# Driver3.net
KiCad netlist of a schematic drawn in Altium Designer
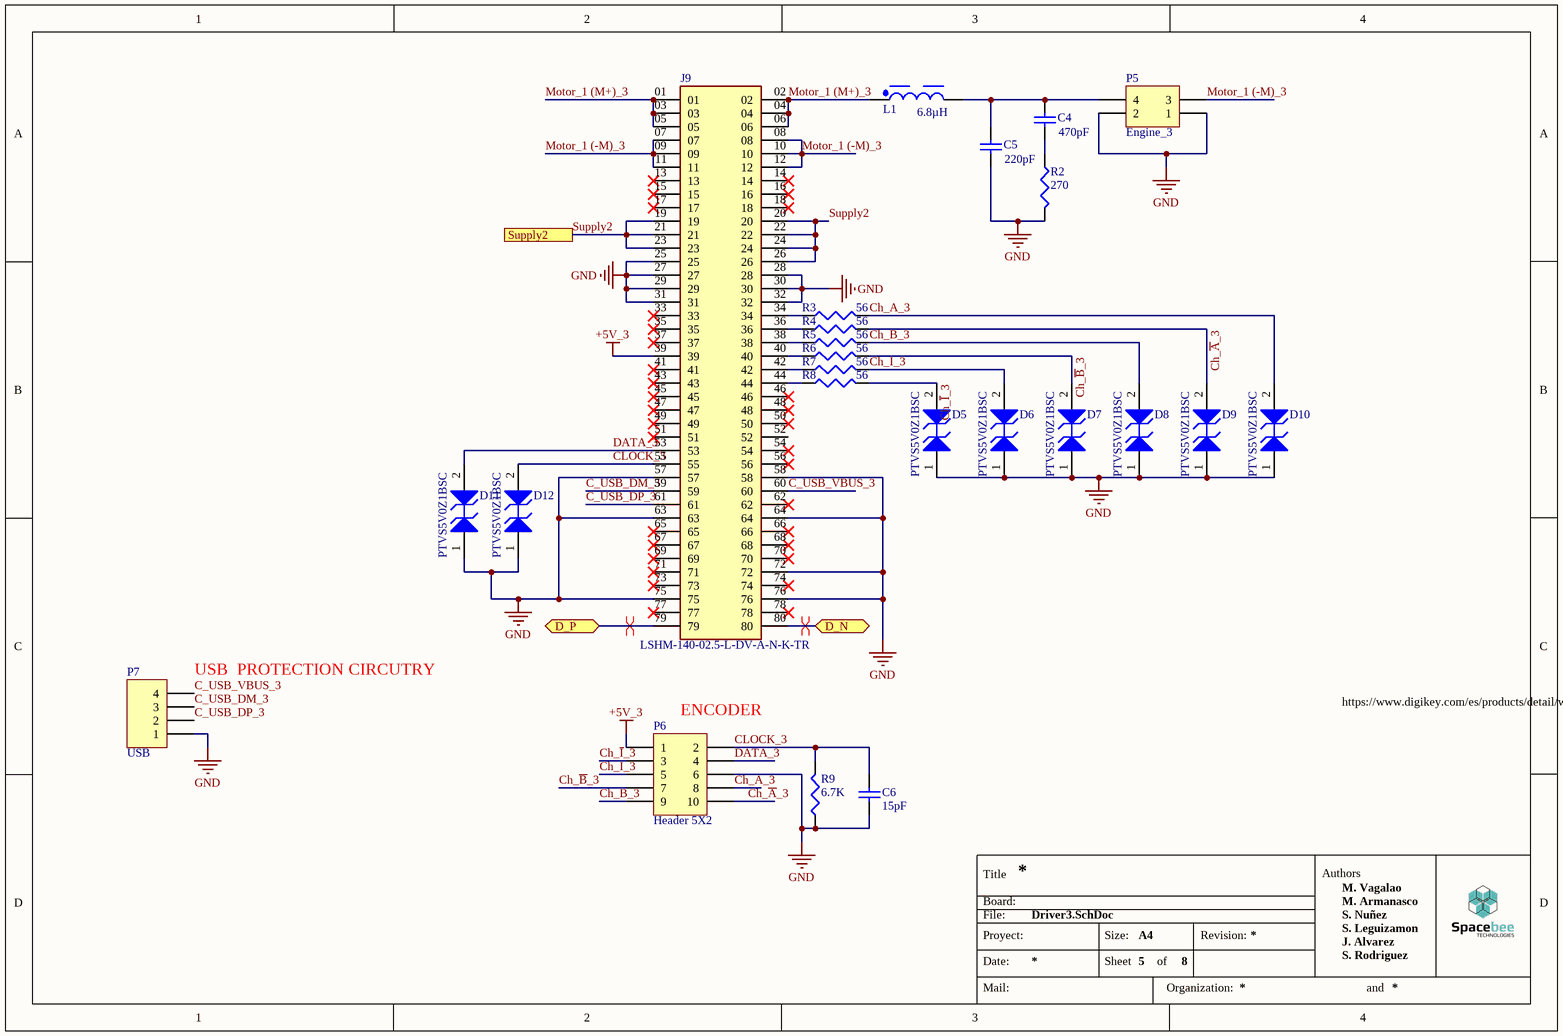
[diagram p0: Driver3.SchDoc]

(export (version "E")
  (design (tool "Eeschema 10.0.6"))
  (components
    (comp (ref "C4")
      (value "470pF")
      (footprint "1608[0603]")
      (description "Capacitor (Semiconductor SIM Model)")
      (fields (field (name "Comment") "Cap Semi") (field (name "PUBLISHER") "Altium Limited"))
      (libsource (lib "Miscellaneous Devices") (part "Cap Semi"))
    )
    (comp (ref "C5")
      (value "220pF")
      (footprint "1608[0603]")
      (description "Capacitor (Semiconductor SIM Model)")
      (fields (field (name "Comment") "Cap Semi") (field (name "PUBLISHER") "Altium Limited"))
      (libsource (lib "Miscellaneous Devices") (part "Cap Semi"))
    )
    (comp (ref "C6")
      (value "15pF")
      (footprint "6-0805_L")
      (description "Capacitor (Semiconductor SIM Model)")
      (fields (field (name "Comment") "Cap Semi") (field (name "PUBLISHER") "Altium Limited"))
      (libsource (lib "SpaceBee") (part "Cap 0805"))
    )
    (comp (ref "D5")
      (value "PTVS5V0Z1BSC")
      (footprint "SOD993B")
      (fields (field (name "MANUFACTURER") "On Semiconductor") (field (name "PARTNUMBER") "1SMB16CAT3"))
      (libsource (lib "DriverLib") (part "PTVS5V0Z1BSC"))
    )
    (comp (ref "D6")
      (value "PTVS5V0Z1BSC")
      (footprint "SOD993B")
      (fields (field (name "MANUFACTURER") "On Semiconductor") (field (name "PARTNUMBER") "1SMB16CAT3"))
      (libsource (lib "DriverLib") (part "PTVS5V0Z1BSC"))
    )
    (comp (ref "D7")
      (value "PTVS5V0Z1BSC")
      (footprint "SOD993B")
      (fields (field (name "MANUFACTURER") "On Semiconductor") (field (name "PARTNUMBER") "1SMB16CAT3"))
      (libsource (lib "DriverLib") (part "PTVS5V0Z1BSC"))
    )
    (comp (ref "D8")
      (value "PTVS5V0Z1BSC")
      (footprint "SOD993B")
      (fields (field (name "MANUFACTURER") "On Semiconductor") (field (name "PARTNUMBER") "1SMB16CAT3"))
      (libsource (lib "DriverLib") (part "PTVS5V0Z1BSC"))
    )
    (comp (ref "D9")
      (value "PTVS5V0Z1BSC")
      (footprint "SOD993B")
      (fields (field (name "MANUFACTURER") "On Semiconductor") (field (name "PARTNUMBER") "1SMB16CAT3"))
      (libsource (lib "DriverLib") (part "PTVS5V0Z1BSC"))
    )
    (comp (ref "D10")
      (value "PTVS5V0Z1BSC")
      (footprint "SOD993B")
      (fields (field (name "MANUFACTURER") "On Semiconductor") (field (name "PARTNUMBER") "1SMB16CAT3"))
      (libsource (lib "DriverLib") (part "PTVS5V0Z1BSC"))
    )
    (comp (ref "D11")
      (value "PTVS5V0Z1BSC")
      (footprint "SOD993B")
      (fields (field (name "MANUFACTURER") "On Semiconductor") (field (name "PARTNUMBER") "1SMB16CAT3"))
      (libsource (lib "DriverLib") (part "PTVS5V0Z1BSC"))
    )
    (comp (ref "D12")
      (value "PTVS5V0Z1BSC")
      (footprint "SOD993B")
      (fields (field (name "MANUFACTURER") "On Semiconductor") (field (name "PARTNUMBER") "1SMB16CAT3"))
      (libsource (lib "DriverLib") (part "PTVS5V0Z1BSC"))
    )
    (comp (ref "J9")
      (value "LSHM-140-02.5-L-DV-A-N-K-TR")
      (footprint "SAMTEC_LSHM-140-02.5-L-DV-A-N-K-TR")
      (description "LSHM - Samtec 0.50mm Razor Beam High-Speed Hermaphroditic Terminal / Socket Strip.")
      (libsource (lib "DriverLib") (part "LSHM-140-02.5-L-DV-A-N-K-TR"))
    )
    (comp (ref "L1")
      (value "6.8µH")
      (footprint "WE-XHMA_6060")
      (description "WE-XHMA SMD Power Inductor, size 1090, 6.8µH, 10.5A, 7.16mΩ")
      (fields
        (field (name "MANUFACTURER PART NUMBER") "78439369068")
        (field (name "MANUFACTURER") "Wurth Elektronik")
      )
      (libsource (lib "DriverLib") (part "78439369068"))
    )
    (comp (ref "P5")
      (value "Engine_3")
      (footprint "MOLEX_1724480004")
      (description "Header, 2-Pin, Dual row")
      (fields (field (name "PUBLISHER") "Altium Limited"))
      (libsource (lib "SpaceBee") (part "Header 2X2"))
    )
    (comp (ref "P6")
      (value "Header 5X2")
      (footprint "CONN_HIF3FC-14PA-2.54DS(71)_HIR")
      (description "Header, 5-Pin, Dual row")
      (fields (field (name "PUBLISHER") "Altium Limited"))
      (libsource (lib "DriverLib") (part "Header 5X2"))
    )
    (comp (ref "P7")
      (value "USB")
      (footprint "Header 4 SMD")
      (description "Header, 4-Pin")
      (fields (field (name "PUBLISHER") "Altium Limited"))
      (libsource (lib "SpaceBee") (part "Header 4 SMD"))
    )
    (comp (ref "R2")
      (value "270")
      (footprint "J1-0603")
      (description "Resistor")
      (fields (field (name "Comment") "Res3") (field (name "PUBLISHER") "Altium Limited"))
      (libsource (lib "Miscellaneous Devices") (part "Res3"))
    )
    (comp (ref "R3")
      (value "56")
      (footprint "J1-0603")
      (description "Resistor")
      (fields (field (name "Comment") "Res3") (field (name "PUBLISHER") "Altium Limited"))
      (libsource (lib "Miscellaneous Devices") (part "Res3"))
    )
    (comp (ref "R4")
      (value "56")
      (footprint "J1-0603")
      (description "Resistor")
      (fields (field (name "Comment") "Res3") (field (name "PUBLISHER") "Altium Limited"))
      (libsource (lib "Miscellaneous Devices") (part "Res3"))
    )
    (comp (ref "R5")
      (value "56")
      (footprint "J1-0603")
      (description "Resistor")
      (fields (field (name "Comment") "Res3") (field (name "PUBLISHER") "Altium Limited"))
      (libsource (lib "Miscellaneous Devices") (part "Res3"))
    )
    (comp (ref "R6")
      (value "56")
      (footprint "J1-0603")
      (description "Resistor")
      (fields (field (name "Comment") "Res3") (field (name "PUBLISHER") "Altium Limited"))
      (libsource (lib "Miscellaneous Devices") (part "Res3"))
    )
    (comp (ref "R7")
      (value "56")
      (footprint "J1-0603")
      (description "Resistor")
      (fields (field (name "Comment") "Res3") (field (name "PUBLISHER") "Altium Limited"))
      (libsource (lib "Miscellaneous Devices") (part "Res3"))
    )
    (comp (ref "R8")
      (value "56")
      (footprint "J1-0603")
      (description "Resistor")
      (fields (field (name "Comment") "Res3") (field (name "PUBLISHER") "Altium Limited"))
      (libsource (lib "Miscellaneous Devices") (part "Res3"))
    )
    (comp (ref "R9")
      (value "6.7K")
      (footprint "J1-0603")
      (description "Resistor")
      (fields (field (name "Comment") "Res3") (field (name "PUBLISHER") "Altium Limited"))
      (libsource (lib "Miscellaneous Devices") (part "Res3"))
    )
  )
  (nets
    (net (code "1") (name "+5V_3") (class "Default")
      (node (ref "J9") (pin "39") (pinfunction "39_39") (pintype "passive"))
      (node (ref "P6") (pin "1") (pinfunction "1_1") (pintype "passive"))
    )
    (net (code "2") (name "/CLOCK_3") (class "Default")
      (node (ref "C6") (pin "2") (pinfunction "2_2") (pintype "passive"))
      (node (ref "D12") (pin "2") (pinfunction "A2_2") (pintype "passive"))
      (node (ref "J9") (pin "55") (pinfunction "55_55") (pintype "passive"))
      (node (ref "P6") (pin "2") (pinfunction "2_2") (pintype "passive"))
      (node (ref "R9") (pin "2") (pinfunction "2_2") (pintype "passive"))
    )
    (net (code "3") (name "/C_USB_DM_3") (class "Default")
      (node (ref "J9") (pin "59") (pinfunction "59_59") (pintype "passive"))
      (node (ref "P7") (pin "3") (pinfunction "3_3") (pintype "passive"))
    )
    (net (code "4") (name "/C_USB_DP_3") (class "Default")
      (node (ref "J9") (pin "61") (pinfunction "61_61") (pintype "passive"))
      (node (ref "P7") (pin "2") (pinfunction "2_2") (pintype "passive"))
    )
    (net (code "5") (name "/C_USB_VBUS_3") (class "Default")
      (node (ref "J9") (pin "60") (pinfunction "60_60") (pintype "passive"))
      (node (ref "P7") (pin "4") (pinfunction "4_4") (pintype "passive"))
    )
    (net (code "6") (name "/Ch_A_3") (class "Default")
      (node (ref "D10") (pin "2") (pinfunction "A2_2") (pintype "passive"))
      (node (ref "P6") (pin "8") (pinfunction "8_8") (pintype "passive"))
      (node (ref "R3") (pin "2") (pinfunction "2_2") (pintype "passive"))
    )
    (net (code "7") (name "/Ch_B_3") (class "Default")
      (node (ref "D8") (pin "2") (pinfunction "A2_2") (pintype "passive"))
      (node (ref "P6") (pin "9") (pinfunction "9_9") (pintype "passive"))
      (node (ref "R5") (pin "2") (pinfunction "2_2") (pintype "passive"))
    )
    (net (code "8") (name "/Ch_I_3") (class "Default")
      (node (ref "D6") (pin "2") (pinfunction "A2_2") (pintype "passive"))
      (node (ref "P6") (pin "5") (pinfunction "5_5") (pintype "passive"))
      (node (ref "R7") (pin "2") (pinfunction "2_2") (pintype "passive"))
    )
    (net (code "9") (name "/Ch_~{A}_3") (class "Default")
      (node (ref "D9") (pin "2") (pinfunction "A2_2") (pintype "passive"))
      (node (ref "P6") (pin "10") (pinfunction "10_10") (pintype "passive"))
      (node (ref "R4") (pin "2") (pinfunction "2_2") (pintype "passive"))
    )
    (net (code "10") (name "/Ch_~{B}_3") (class "Default")
      (node (ref "D7") (pin "2") (pinfunction "A2_2") (pintype "passive"))
      (node (ref "P6") (pin "7") (pinfunction "7_7") (pintype "passive"))
      (node (ref "R6") (pin "2") (pinfunction "2_2") (pintype "passive"))
    )
    (net (code "11") (name "/Ch_~{I}_3") (class "Default")
      (node (ref "D5") (pin "2") (pinfunction "A2_2") (pintype "passive"))
      (node (ref "P6") (pin "3") (pinfunction "3_3") (pintype "passive"))
      (node (ref "R8") (pin "2") (pinfunction "2_2") (pintype "passive"))
    )
    (net (code "12") (name "/DATA_3") (class "Default")
      (node (ref "D11") (pin "2") (pinfunction "A2_2") (pintype "passive"))
      (node (ref "J9") (pin "53") (pinfunction "53_53") (pintype "passive"))
      (node (ref "P6") (pin "4") (pinfunction "4_4") (pintype "passive"))
    )
    (net (code "13") (name "/D_N") (class "Default")
      (node (ref "J9") (pin "80") (pinfunction "80_80") (pintype "passive"))
    )
    (net (code "14") (name "/D_P") (class "Default")
      (node (ref "J9") (pin "79") (pinfunction "79_79") (pintype "passive"))
    )
    (net (code "15") (name "/Motor_1 (-M)_3") (class "Default")
      (node (ref "J9") (pin "07") (pinfunction "07_07") (pintype "passive"))
      (node (ref "J9") (pin "08") (pinfunction "08_08") (pintype "passive"))
      (node (ref "J9") (pin "09") (pinfunction "09_09") (pintype "passive"))
      (node (ref "J9") (pin "10") (pinfunction "10_10") (pintype "passive"))
      (node (ref "J9") (pin "11") (pinfunction "11_11") (pintype "passive"))
      (node (ref "J9") (pin "12") (pinfunction "12_12") (pintype "passive"))
      (node (ref "P5") (pin "3") (pinfunction "3_3") (pintype "passive"))
    )
    (net (code "16") (name "/Motor_1 (M+)_3") (class "Default")
      (node (ref "J9") (pin "01") (pinfunction "01_01") (pintype "passive"))
      (node (ref "J9") (pin "02") (pinfunction "02_02") (pintype "passive"))
      (node (ref "J9") (pin "03") (pinfunction "03_03") (pintype "passive"))
      (node (ref "J9") (pin "04") (pinfunction "04_04") (pintype "passive"))
      (node (ref "J9") (pin "05") (pinfunction "05_05") (pintype "passive"))
      (node (ref "J9") (pin "06") (pinfunction "06_06") (pintype "passive"))
      (node (ref "L1") (pin "1") (pinfunction "1_1") (pintype "passive"))
    )
    (net (code "17") (name "/Supply2") (class "Default")
      (node (ref "J9") (pin "19") (pinfunction "19_19") (pintype "passive"))
      (node (ref "J9") (pin "20") (pinfunction "20_20") (pintype "passive"))
      (node (ref "J9") (pin "21") (pinfunction "21_21") (pintype "passive"))
      (node (ref "J9") (pin "22") (pinfunction "22_22") (pintype "passive"))
      (node (ref "J9") (pin "23") (pinfunction "23_23") (pintype "passive"))
      (node (ref "J9") (pin "24") (pinfunction "24_24") (pintype "passive"))
      (node (ref "J9") (pin "26") (pinfunction "26_26") (pintype "passive"))
    )
    (net (code "18") (name "GND") (class "Default")
      (node (ref "C5") (pin "2") (pinfunction "2_2") (pintype "passive"))
      (node (ref "C6") (pin "1") (pinfunction "1_1") (pintype "passive"))
      (node (ref "D10") (pin "1") (pinfunction "A1_1") (pintype "passive"))
      (node (ref "D11") (pin "1") (pinfunction "A1_1") (pintype "passive"))
      (node (ref "D12") (pin "1") (pinfunction "A1_1") (pintype "passive"))
      (node (ref "D5") (pin "1") (pinfunction "A1_1") (pintype "passive"))
      (node (ref "D6") (pin "1") (pinfunction "A1_1") (pintype "passive"))
      (node (ref "D7") (pin "1") (pinfunction "A1_1") (pintype "passive"))
      (node (ref "D8") (pin "1") (pinfunction "A1_1") (pintype "passive"))
      (node (ref "D9") (pin "1") (pinfunction "A1_1") (pintype "passive"))
      (node (ref "J9") (pin "25") (pinfunction "25_25") (pintype "passive"))
      (node (ref "J9") (pin "27") (pinfunction "27_27") (pintype "passive"))
      (node (ref "J9") (pin "28") (pinfunction "28_28") (pintype "passive"))
      (node (ref "J9") (pin "29") (pinfunction "29_29") (pintype "passive"))
      (node (ref "J9") (pin "30") (pinfunction "30_30") (pintype "passive"))
      (node (ref "J9") (pin "31") (pinfunction "31_31") (pintype "passive"))
      (node (ref "J9") (pin "32") (pinfunction "32_32") (pintype "passive"))
      (node (ref "J9") (pin "57") (pinfunction "57_57") (pintype "passive"))
      (node (ref "J9") (pin "58") (pinfunction "58_58") (pintype "passive"))
      (node (ref "J9") (pin "63") (pinfunction "63_63") (pintype "passive"))
      (node (ref "J9") (pin "64") (pinfunction "64_64") (pintype "passive"))
      (node (ref "J9") (pin "72") (pinfunction "72_72") (pintype "passive"))
      (node (ref "J9") (pin "75") (pinfunction "75_75") (pintype "passive"))
      (node (ref "J9") (pin "76") (pinfunction "76_76") (pintype "passive"))
      (node (ref "P5") (pin "1") (pinfunction "1_1") (pintype "passive"))
      (node (ref "P5") (pin "2") (pinfunction "2_2") (pintype "passive"))
      (node (ref "P6") (pin "6") (pinfunction "6_6") (pintype "passive"))
      (node (ref "P7") (pin "1") (pinfunction "1_1") (pintype "passive"))
      (node (ref "R2") (pin "2") (pinfunction "2_2") (pintype "passive"))
      (node (ref "R9") (pin "1") (pinfunction "1_1") (pintype "passive"))
    )
    (net (code "19") (name "Net-(C4-Pad1)") (class "Default")
      (node (ref "C4") (pin "1") (pinfunction "1_1") (pintype "passive"))
      (node (ref "C5") (pin "1") (pinfunction "1_1") (pintype "passive"))
      (node (ref "L1") (pin "2") (pinfunction "2_2") (pintype "passive"))
      (node (ref "P5") (pin "4") (pinfunction "4_4") (pintype "passive"))
    )
    (net (code "20") (name "Net-(C4-Pad2)") (class "Default")
      (node (ref "C4") (pin "2") (pinfunction "2_2") (pintype "passive"))
      (node (ref "R2") (pin "1") (pinfunction "1_1") (pintype "passive"))
    )
    (net (code "21") (name "Net-(J9-Pad34)") (class "Default")
      (node (ref "J9") (pin "34") (pinfunction "34_34") (pintype "passive"))
      (node (ref "R3") (pin "1") (pinfunction "1_1") (pintype "passive"))
    )
    (net (code "22") (name "Net-(J9-Pad36)") (class "Default")
      (node (ref "J9") (pin "36") (pinfunction "36_36") (pintype "passive"))
      (node (ref "R4") (pin "1") (pinfunction "1_1") (pintype "passive"))
    )
    (net (code "23") (name "Net-(J9-Pad38)") (class "Default")
      (node (ref "J9") (pin "38") (pinfunction "38_38") (pintype "passive"))
      (node (ref "R5") (pin "1") (pinfunction "1_1") (pintype "passive"))
    )
    (net (code "24") (name "Net-(J9-Pad40)") (class "Default")
      (node (ref "J9") (pin "40") (pinfunction "40_40") (pintype "passive"))
      (node (ref "R6") (pin "1") (pinfunction "1_1") (pintype "passive"))
    )
    (net (code "25") (name "Net-(J9-Pad42)") (class "Default")
      (node (ref "J9") (pin "42") (pinfunction "42_42") (pintype "passive"))
      (node (ref "R7") (pin "1") (pinfunction "1_1") (pintype "passive"))
    )
    (net (code "26") (name "Net-(J9-Pad44)") (class "Default")
      (node (ref "J9") (pin "44") (pinfunction "44_44") (pintype "passive"))
      (node (ref "R8") (pin "1") (pinfunction "1_1") (pintype "passive"))
    )
    (net (code "27") (name "unconnected-(J9-Pad13)") (class "Default")
      (node (ref "J9") (pin "13") (pinfunction "13_13") (pintype "passive+no_connect"))
    )
    (net (code "28") (name "unconnected-(J9-Pad14)") (class "Default")
      (node (ref "J9") (pin "14") (pinfunction "14_14") (pintype "passive+no_connect"))
    )
    (net (code "29") (name "unconnected-(J9-Pad15)") (class "Default")
      (node (ref "J9") (pin "15") (pinfunction "15_15") (pintype "passive+no_connect"))
    )
    (net (code "30") (name "unconnected-(J9-Pad16)") (class "Default")
      (node (ref "J9") (pin "16") (pinfunction "16_16") (pintype "passive+no_connect"))
    )
    (net (code "31") (name "unconnected-(J9-Pad17)") (class "Default")
      (node (ref "J9") (pin "17") (pinfunction "17_17") (pintype "passive+no_connect"))
    )
    (net (code "32") (name "unconnected-(J9-Pad18)") (class "Default")
      (node (ref "J9") (pin "18") (pinfunction "18_18") (pintype "passive+no_connect"))
    )
    (net (code "33") (name "unconnected-(J9-Pad33)") (class "Default")
      (node (ref "J9") (pin "33") (pinfunction "33_33") (pintype "passive+no_connect"))
    )
    (net (code "34") (name "unconnected-(J9-Pad35)") (class "Default")
      (node (ref "J9") (pin "35") (pinfunction "35_35") (pintype "passive+no_connect"))
    )
    (net (code "35") (name "unconnected-(J9-Pad37)") (class "Default")
      (node (ref "J9") (pin "37") (pinfunction "37_37") (pintype "passive+no_connect"))
    )
    (net (code "36") (name "unconnected-(J9-Pad41)") (class "Default")
      (node (ref "J9") (pin "41") (pinfunction "41_41") (pintype "passive+no_connect"))
    )
    (net (code "37") (name "unconnected-(J9-Pad43)") (class "Default")
      (node (ref "J9") (pin "43") (pinfunction "43_43") (pintype "passive+no_connect"))
    )
    (net (code "38") (name "unconnected-(J9-Pad45)") (class "Default")
      (node (ref "J9") (pin "45") (pinfunction "45_45") (pintype "passive+no_connect"))
    )
    (net (code "39") (name "unconnected-(J9-Pad46)") (class "Default")
      (node (ref "J9") (pin "46") (pinfunction "46_46") (pintype "passive+no_connect"))
    )
    (net (code "40") (name "unconnected-(J9-Pad47)") (class "Default")
      (node (ref "J9") (pin "47") (pinfunction "47_47") (pintype "passive+no_connect"))
    )
    (net (code "41") (name "unconnected-(J9-Pad48)") (class "Default")
      (node (ref "J9") (pin "48") (pinfunction "48_48") (pintype "passive+no_connect"))
    )
    (net (code "42") (name "unconnected-(J9-Pad49)") (class "Default")
      (node (ref "J9") (pin "49") (pinfunction "49_49") (pintype "passive+no_connect"))
    )
    (net (code "43") (name "unconnected-(J9-Pad50)") (class "Default")
      (node (ref "J9") (pin "50") (pinfunction "50_50") (pintype "passive+no_connect"))
    )
    (net (code "44") (name "unconnected-(J9-Pad51)") (class "Default")
      (node (ref "J9") (pin "51") (pinfunction "51_51") (pintype "passive+no_connect"))
    )
    (net (code "45") (name "unconnected-(J9-Pad52)") (class "Default")
      (node (ref "J9") (pin "52") (pinfunction "52_52") (pintype "passive"))
    )
    (net (code "46") (name "unconnected-(J9-Pad54)") (class "Default")
      (node (ref "J9") (pin "54") (pinfunction "54_54") (pintype "passive+no_connect"))
    )
    (net (code "47") (name "unconnected-(J9-Pad56)") (class "Default")
      (node (ref "J9") (pin "56") (pinfunction "56_56") (pintype "passive+no_connect"))
    )
    (net (code "48") (name "unconnected-(J9-Pad62)") (class "Default")
      (node (ref "J9") (pin "62") (pinfunction "62_62") (pintype "passive+no_connect"))
    )
    (net (code "49") (name "unconnected-(J9-Pad65)") (class "Default")
      (node (ref "J9") (pin "65") (pinfunction "65_65") (pintype "passive+no_connect"))
    )
    (net (code "50") (name "unconnected-(J9-Pad66)") (class "Default")
      (node (ref "J9") (pin "66") (pinfunction "66_66") (pintype "passive+no_connect"))
    )
    (net (code "51") (name "unconnected-(J9-Pad67)") (class "Default")
      (node (ref "J9") (pin "67") (pinfunction "67_67") (pintype "passive+no_connect"))
    )
    (net (code "52") (name "unconnected-(J9-Pad68)") (class "Default")
      (node (ref "J9") (pin "68") (pinfunction "68_68") (pintype "passive+no_connect"))
    )
    (net (code "53") (name "unconnected-(J9-Pad69)") (class "Default")
      (node (ref "J9") (pin "69") (pinfunction "69_69") (pintype "passive+no_connect"))
    )
    (net (code "54") (name "unconnected-(J9-Pad70)") (class "Default")
      (node (ref "J9") (pin "70") (pinfunction "70_70") (pintype "passive+no_connect"))
    )
    (net (code "55") (name "unconnected-(J9-Pad71)") (class "Default")
      (node (ref "J9") (pin "71") (pinfunction "71_71") (pintype "passive+no_connect"))
    )
    (net (code "56") (name "unconnected-(J9-Pad73)") (class "Default")
      (node (ref "J9") (pin "73") (pinfunction "73_73") (pintype "passive+no_connect"))
    )
    (net (code "57") (name "unconnected-(J9-Pad74)") (class "Default")
      (node (ref "J9") (pin "74") (pinfunction "74_74") (pintype "passive+no_connect"))
    )
    (net (code "58") (name "unconnected-(J9-Pad77)") (class "Default")
      (node (ref "J9") (pin "77") (pinfunction "77_77") (pintype "passive+no_connect"))
    )
    (net (code "59") (name "unconnected-(J9-Pad78)") (class "Default")
      (node (ref "J9") (pin "78") (pinfunction "78_78") (pintype "passive+no_connect"))
    )
  )
)
